# IR-ARRAY.net
KiCad netlist of a schematic drawn in Altium Designer
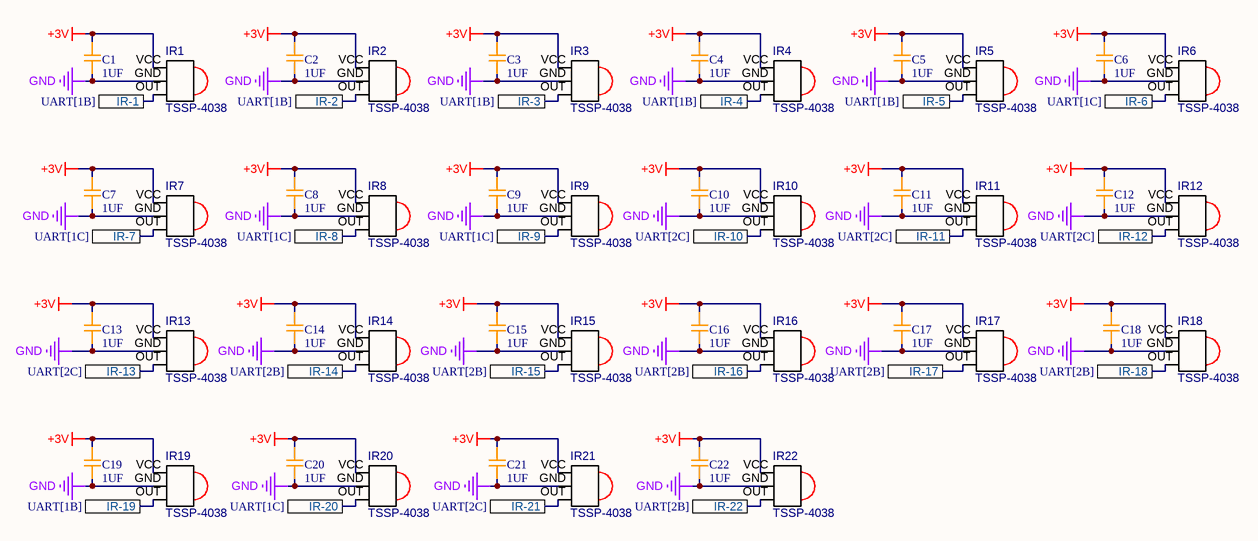
[diagram p0: IR-ARRAY.SchDoc]

(export (version "E")
  (design (tool "Eeschema 10.0.6"))
  (components
    (comp (ref "C1")
      (value "1UF")
      (footprint "CAP_0603")
      (description "Capacitor SMD 0603 generic")
      (libsource (lib "RC") (part "CAP_0603"))
    )
    (comp (ref "C2")
      (value "1UF")
      (footprint "CAP_0603")
      (description "Capacitor SMD 0603 generic")
      (libsource (lib "RC") (part "CAP_0603"))
    )
    (comp (ref "C3")
      (value "1UF")
      (footprint "CAP_0603")
      (description "Capacitor SMD 0603 generic")
      (libsource (lib "RC") (part "CAP_0603"))
    )
    (comp (ref "C4")
      (value "1UF")
      (footprint "CAP_0603")
      (description "Capacitor SMD 0603 generic")
      (libsource (lib "RC") (part "CAP_0603"))
    )
    (comp (ref "C5")
      (value "1UF")
      (footprint "CAP_0603")
      (description "Capacitor SMD 0603 generic")
      (libsource (lib "RC") (part "CAP_0603"))
    )
    (comp (ref "C6")
      (value "1UF")
      (footprint "CAP_0603")
      (description "Capacitor SMD 0603 generic")
      (libsource (lib "RC") (part "CAP_0603"))
    )
    (comp (ref "C7")
      (value "1UF")
      (footprint "CAP_0603")
      (description "Capacitor SMD 0603 generic")
      (libsource (lib "RC") (part "CAP_0603"))
    )
    (comp (ref "C8")
      (value "1UF")
      (footprint "CAP_0603")
      (description "Capacitor SMD 0603 generic")
      (libsource (lib "RC") (part "CAP_0603"))
    )
    (comp (ref "C9")
      (value "1UF")
      (footprint "CAP_0603")
      (description "Capacitor SMD 0603 generic")
      (libsource (lib "RC") (part "CAP_0603"))
    )
    (comp (ref "C10")
      (value "1UF")
      (footprint "CAP_0603")
      (description "Capacitor SMD 0603 generic")
      (libsource (lib "RC") (part "CAP_0603"))
    )
    (comp (ref "C11")
      (value "1UF")
      (footprint "CAP_0603")
      (description "Capacitor SMD 0603 generic")
      (libsource (lib "RC") (part "CAP_0603"))
    )
    (comp (ref "C12")
      (value "1UF")
      (footprint "CAP_0603")
      (description "Capacitor SMD 0603 generic")
      (libsource (lib "RC") (part "CAP_0603"))
    )
    (comp (ref "C13")
      (value "1UF")
      (footprint "CAP_0603")
      (description "Capacitor SMD 0603 generic")
      (libsource (lib "RC") (part "CAP_0603"))
    )
    (comp (ref "C14")
      (value "1UF")
      (footprint "CAP_0603")
      (description "Capacitor SMD 0603 generic")
      (libsource (lib "RC") (part "CAP_0603"))
    )
    (comp (ref "C15")
      (value "1UF")
      (footprint "CAP_0603")
      (description "Capacitor SMD 0603 generic")
      (libsource (lib "RC") (part "CAP_0603"))
    )
    (comp (ref "C16")
      (value "1UF")
      (footprint "CAP_0603")
      (description "Capacitor SMD 0603 generic")
      (libsource (lib "RC") (part "CAP_0603"))
    )
    (comp (ref "C17")
      (value "1UF")
      (footprint "CAP_0603")
      (description "Capacitor SMD 0603 generic")
      (libsource (lib "RC") (part "CAP_0603"))
    )
    (comp (ref "C18")
      (value "1UF")
      (footprint "CAP_0603")
      (description "Capacitor SMD 0603 generic")
      (libsource (lib "RC") (part "CAP_0603"))
    )
    (comp (ref "C19")
      (value "1UF")
      (footprint "CAP_0603")
      (description "Capacitor SMD 0603 generic")
      (libsource (lib "RC") (part "CAP_0603"))
    )
    (comp (ref "C20")
      (value "1UF")
      (footprint "CAP_0603")
      (description "Capacitor SMD 0603 generic")
      (libsource (lib "RC") (part "CAP_0603"))
    )
    (comp (ref "C21")
      (value "1UF")
      (footprint "CAP_0603")
      (description "Capacitor SMD 0603 generic")
      (libsource (lib "RC") (part "CAP_0603"))
    )
    (comp (ref "C22")
      (value "1UF")
      (footprint "CAP_0603")
      (description "Capacitor SMD 0603 generic")
      (libsource (lib "RC") (part "CAP_0603"))
    )
    (comp (ref "IR1") (value "TSSP-4038") (footprint "TSSP-4038") (libsource (lib "RC") (part "TSSP-4038")))
    (comp (ref "IR2") (value "TSSP-4038") (footprint "TSSP-4038") (libsource (lib "RC") (part "TSSP-4038")))
    (comp (ref "IR3") (value "TSSP-4038") (footprint "TSSP-4038") (libsource (lib "RC") (part "TSSP-4038")))
    (comp (ref "IR4") (value "TSSP-4038") (footprint "TSSP-4038") (libsource (lib "RC") (part "TSSP-4038")))
    (comp (ref "IR5") (value "TSSP-4038") (footprint "TSSP-4038") (libsource (lib "RC") (part "TSSP-4038")))
    (comp (ref "IR6") (value "TSSP-4038") (footprint "TSSP-4038") (libsource (lib "RC") (part "TSSP-4038")))
    (comp (ref "IR7") (value "TSSP-4038") (footprint "TSSP-4038") (libsource (lib "RC") (part "TSSP-4038")))
    (comp (ref "IR8") (value "TSSP-4038") (footprint "TSSP-4038") (libsource (lib "RC") (part "TSSP-4038")))
    (comp (ref "IR9") (value "TSSP-4038") (footprint "TSSP-4038") (libsource (lib "RC") (part "TSSP-4038")))
    (comp (ref "IR10") (value "TSSP-4038") (footprint "TSSP-4038") (libsource (lib "RC") (part "TSSP-4038")))
    (comp (ref "IR11") (value "TSSP-4038") (footprint "TSSP-4038") (libsource (lib "RC") (part "TSSP-4038")))
    (comp (ref "IR12") (value "TSSP-4038") (footprint "TSSP-4038") (libsource (lib "RC") (part "TSSP-4038")))
    (comp (ref "IR13") (value "TSSP-4038") (footprint "TSSP-4038") (libsource (lib "RC") (part "TSSP-4038")))
    (comp (ref "IR14") (value "TSSP-4038") (footprint "TSSP-4038") (libsource (lib "RC") (part "TSSP-4038")))
    (comp (ref "IR15") (value "TSSP-4038") (footprint "TSSP-4038") (libsource (lib "RC") (part "TSSP-4038")))
    (comp (ref "IR16") (value "TSSP-4038") (footprint "TSSP-4038") (libsource (lib "RC") (part "TSSP-4038")))
    (comp (ref "IR17") (value "TSSP-4038") (footprint "TSSP-4038") (libsource (lib "RC") (part "TSSP-4038")))
    (comp (ref "IR18") (value "TSSP-4038") (footprint "TSSP-4038") (libsource (lib "RC") (part "TSSP-4038")))
    (comp (ref "IR19") (value "TSSP-4038") (footprint "TSSP-4038") (libsource (lib "RC") (part "TSSP-4038")))
    (comp (ref "IR20") (value "TSSP-4038") (footprint "TSSP-4038") (libsource (lib "RC") (part "TSSP-4038")))
    (comp (ref "IR21") (value "TSSP-4038") (footprint "TSSP-4038") (libsource (lib "RC") (part "TSSP-4038")))
    (comp (ref "IR22") (value "TSSP-4038") (footprint "TSSP-4038") (libsource (lib "RC") (part "TSSP-4038")))
  )
  (nets
    (net (code "1") (name "+3V") (class "Default")
      (node (ref "C1") (pin "1") (pintype "passive"))
      (node (ref "C10") (pin "1") (pintype "passive"))
      (node (ref "C11") (pin "1") (pintype "passive"))
      (node (ref "C12") (pin "1") (pintype "passive"))
      (node (ref "C13") (pin "1") (pintype "passive"))
      (node (ref "C14") (pin "1") (pintype "passive"))
      (node (ref "C15") (pin "1") (pintype "passive"))
      (node (ref "C16") (pin "1") (pintype "passive"))
      (node (ref "C17") (pin "1") (pintype "passive"))
      (node (ref "C18") (pin "1") (pintype "passive"))
      (node (ref "C19") (pin "1") (pintype "passive"))
      (node (ref "C2") (pin "1") (pintype "passive"))
      (node (ref "C20") (pin "1") (pintype "passive"))
      (node (ref "C21") (pin "1") (pintype "passive"))
      (node (ref "C22") (pin "1") (pintype "passive"))
      (node (ref "C3") (pin "1") (pintype "passive"))
      (node (ref "C4") (pin "1") (pintype "passive"))
      (node (ref "C5") (pin "1") (pintype "passive"))
      (node (ref "C6") (pin "1") (pintype "passive"))
      (node (ref "C7") (pin "1") (pintype "passive"))
      (node (ref "C8") (pin "1") (pintype "passive"))
      (node (ref "C9") (pin "1") (pintype "passive"))
      (node (ref "IR1") (pin "VCC") (pintype "passive"))
      (node (ref "IR10") (pin "VCC") (pintype "passive"))
      (node (ref "IR11") (pin "VCC") (pintype "passive"))
      (node (ref "IR12") (pin "VCC") (pintype "passive"))
      (node (ref "IR13") (pin "VCC") (pintype "passive"))
      (node (ref "IR14") (pin "VCC") (pintype "passive"))
      (node (ref "IR15") (pin "VCC") (pintype "passive"))
      (node (ref "IR16") (pin "VCC") (pintype "passive"))
      (node (ref "IR17") (pin "VCC") (pintype "passive"))
      (node (ref "IR18") (pin "VCC") (pintype "passive"))
      (node (ref "IR19") (pin "VCC") (pintype "passive"))
      (node (ref "IR2") (pin "VCC") (pintype "passive"))
      (node (ref "IR20") (pin "VCC") (pintype "passive"))
      (node (ref "IR21") (pin "VCC") (pintype "passive"))
      (node (ref "IR22") (pin "VCC") (pintype "passive"))
      (node (ref "IR3") (pin "VCC") (pintype "passive"))
      (node (ref "IR4") (pin "VCC") (pintype "passive"))
      (node (ref "IR5") (pin "VCC") (pintype "passive"))
      (node (ref "IR6") (pin "VCC") (pintype "passive"))
      (node (ref "IR7") (pin "VCC") (pintype "passive"))
      (node (ref "IR8") (pin "VCC") (pintype "passive"))
      (node (ref "IR9") (pin "VCC") (pintype "passive"))
    )
    (net (code "2") (name "/IR-1") (class "Default") (node (ref "IR1") (pin "OUT") (pintype "passive")))
    (net (code "3") (name "/IR-2") (class "Default") (node (ref "IR2") (pin "OUT") (pintype "passive")))
    (net (code "4") (name "/IR-3") (class "Default") (node (ref "IR3") (pin "OUT") (pintype "passive")))
    (net (code "5") (name "/IR-4") (class "Default") (node (ref "IR4") (pin "OUT") (pintype "passive")))
    (net (code "6") (name "/IR-5") (class "Default") (node (ref "IR5") (pin "OUT") (pintype "passive")))
    (net (code "7") (name "/IR-6") (class "Default") (node (ref "IR6") (pin "OUT") (pintype "passive")))
    (net (code "8") (name "/IR-7") (class "Default") (node (ref "IR7") (pin "OUT") (pintype "passive")))
    (net (code "9") (name "/IR-8") (class "Default") (node (ref "IR8") (pin "OUT") (pintype "passive")))
    (net (code "10") (name "/IR-9") (class "Default") (node (ref "IR9") (pin "OUT") (pintype "passive")))
    (net (code "11") (name "/IR-10") (class "Default") (node (ref "IR10") (pin "OUT") (pintype "passive")))
    (net (code "12") (name "/IR-11") (class "Default") (node (ref "IR11") (pin "OUT") (pintype "passive")))
    (net (code "13") (name "/IR-12") (class "Default") (node (ref "IR12") (pin "OUT") (pintype "passive")))
    (net (code "14") (name "/IR-13") (class "Default") (node (ref "IR13") (pin "OUT") (pintype "passive")))
    (net (code "15") (name "/IR-14") (class "Default") (node (ref "IR14") (pin "OUT") (pintype "passive")))
    (net (code "16") (name "/IR-15") (class "Default") (node (ref "IR15") (pin "OUT") (pintype "passive")))
    (net (code "17") (name "/IR-16") (class "Default") (node (ref "IR16") (pin "OUT") (pintype "passive")))
    (net (code "18") (name "/IR-17") (class "Default") (node (ref "IR17") (pin "OUT") (pintype "passive")))
    (net (code "19") (name "/IR-18") (class "Default") (node (ref "IR18") (pin "OUT") (pintype "passive")))
    (net (code "20") (name "/IR-19") (class "Default") (node (ref "IR19") (pin "OUT") (pintype "passive")))
    (net (code "21") (name "/IR-20") (class "Default") (node (ref "IR20") (pin "OUT") (pintype "passive")))
    (net (code "22") (name "/IR-21") (class "Default") (node (ref "IR21") (pin "OUT") (pintype "passive")))
    (net (code "23") (name "/IR-22") (class "Default") (node (ref "IR22") (pin "OUT") (pintype "passive")))
    (net (code "24") (name "GND") (class "Default")
      (node (ref "C1") (pin "2") (pintype "passive"))
      (node (ref "C10") (pin "2") (pintype "passive"))
      (node (ref "C11") (pin "2") (pintype "passive"))
      (node (ref "C12") (pin "2") (pintype "passive"))
      (node (ref "C13") (pin "2") (pintype "passive"))
      (node (ref "C14") (pin "2") (pintype "passive"))
      (node (ref "C15") (pin "2") (pintype "passive"))
      (node (ref "C16") (pin "2") (pintype "passive"))
      (node (ref "C17") (pin "2") (pintype "passive"))
      (node (ref "C18") (pin "2") (pintype "passive"))
      (node (ref "C19") (pin "2") (pintype "passive"))
      (node (ref "C2") (pin "2") (pintype "passive"))
      (node (ref "C20") (pin "2") (pintype "passive"))
      (node (ref "C21") (pin "2") (pintype "passive"))
      (node (ref "C22") (pin "2") (pintype "passive"))
      (node (ref "C3") (pin "2") (pintype "passive"))
      (node (ref "C4") (pin "2") (pintype "passive"))
      (node (ref "C5") (pin "2") (pintype "passive"))
      (node (ref "C6") (pin "2") (pintype "passive"))
      (node (ref "C7") (pin "2") (pintype "passive"))
      (node (ref "C8") (pin "2") (pintype "passive"))
      (node (ref "C9") (pin "2") (pintype "passive"))
      (node (ref "IR1") (pin "GND") (pintype "passive"))
      (node (ref "IR10") (pin "GND") (pintype "passive"))
      (node (ref "IR11") (pin "GND") (pintype "passive"))
      (node (ref "IR12") (pin "GND") (pintype "passive"))
      (node (ref "IR13") (pin "GND") (pintype "passive"))
      (node (ref "IR14") (pin "GND") (pintype "passive"))
      (node (ref "IR15") (pin "GND") (pintype "passive"))
      (node (ref "IR16") (pin "GND") (pintype "passive"))
      (node (ref "IR17") (pin "GND") (pintype "passive"))
      (node (ref "IR18") (pin "GND") (pintype "passive"))
      (node (ref "IR19") (pin "GND") (pintype "passive"))
      (node (ref "IR2") (pin "GND") (pintype "passive"))
      (node (ref "IR20") (pin "GND") (pintype "passive"))
      (node (ref "IR21") (pin "GND") (pintype "passive"))
      (node (ref "IR22") (pin "GND") (pintype "passive"))
      (node (ref "IR3") (pin "GND") (pintype "passive"))
      (node (ref "IR4") (pin "GND") (pintype "passive"))
      (node (ref "IR5") (pin "GND") (pintype "passive"))
      (node (ref "IR6") (pin "GND") (pintype "passive"))
      (node (ref "IR7") (pin "GND") (pintype "passive"))
      (node (ref "IR8") (pin "GND") (pintype "passive"))
      (node (ref "IR9") (pin "GND") (pintype "passive"))
    )
  )
)
